# FET_Driver.net
KiCad netlist of a schematic drawn in Altium Designer
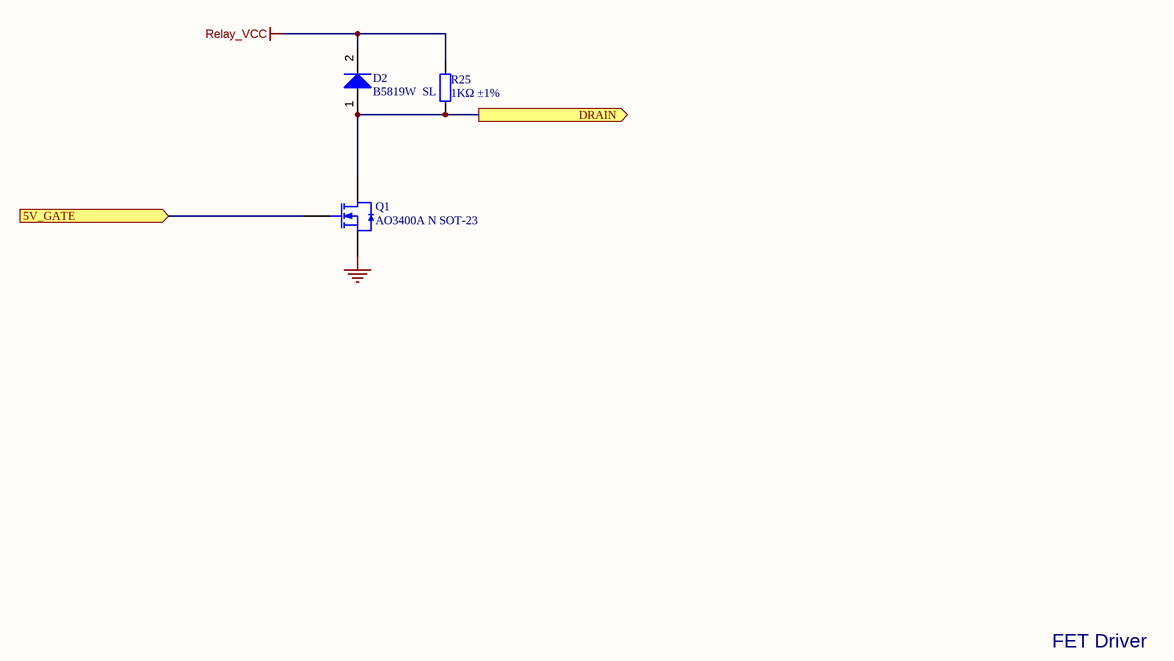
[diagram p0: FET_Driver.SchDoc]

(export (version "E")
  (design (tool "Eeschema 10.0.6"))
  (components
    (comp (ref "D2")
      (value "B5819W  SL")
      (footprint "SOD-123")
      (description "Schottky Diode")
      (libsource (lib "Diode") (part "SOD-123 B5819W  SL"))
    )
    (comp (ref "Q1")
      (value "AO3400A N SOT-23")
      (footprint "SOT-23-3L")
      (description "N MOSFET")
      (libsource (lib "MOS") (part "AO3400A N道沟 X0YV1T SOT-23"))
    )
    (comp (ref "R25")
      (value "1KΩ ±1%")
      (footprint "0402_R")
      (description "Chip resistor")
      (fields (field (name "MANUFACTURER") "Uniroyal Elec") (field (name "PARTNUMBER") "0402WGF1001TCE"))
      (libsource (lib "RES") (part "0402 1K (1001) 1%"))
    )
  )
  (nets
    (net (code "1") (name "/5V_GATE") (class "Default")
      (node (ref "Q1") (pin "1") (pinfunction "G_1") (pintype "passive"))
    )
    (net (code "2") (name "/DRAIN") (class "Default")
      (node (ref "D2") (pin "1") (pinfunction "A_1") (pintype "passive"))
      (node (ref "Q1") (pin "3") (pinfunction "D_3") (pintype "passive"))
      (node (ref "R25") (pin "1") (pinfunction "1_1") (pintype "passive"))
    )
    (net (code "3") (name "GND") (class "Default")
      (node (ref "Q1") (pin "2") (pinfunction "S_2") (pintype "passive"))
    )
    (net (code "4") (name "Relay_VCC") (class "Default")
      (node (ref "D2") (pin "2") (pinfunction "K_2") (pintype "passive"))
      (node (ref "R25") (pin "2") (pinfunction "2_2") (pintype "passive"))
    )
  )
)
